# MC_power_en.net
KiCad netlist of a schematic drawn in Altium Designer
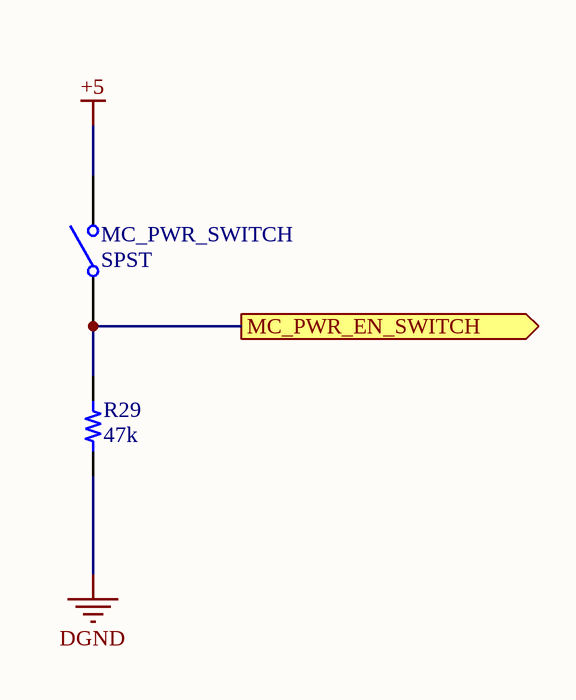
[diagram p0: MC_power_en.SchDoc]

(export (version "E")
  (design (tool "Eeschema 10.0.6"))
  (components
    (comp (ref "MC_PWR_SWITCH")
      (value "SPST")
      (footprint "M2011SS1W01/UC")
      (fields (field (name "MFRPARTNO") "M2011SS1W01_UC"))
      (libsource (lib "Altium-Lib") (part "SPST"))
    )
    (comp (ref "R29")
      (value "47k")
      (footprint "RES 0805/2012")
      (fields
        (field (name "TOLERANCE") "10%")
        (field (name "POWER") "1/4W")
        (field (name "Comment") "Resistor 47k 0805 1/4W 10%")
        (field (name "CREATED_BY") "Nick Mah")
      )
      (libsource (lib "Altium-Lib") (part "Resistor"))
    )
  )
  (nets
    (net (code "1") (name "+5") (class "Default")
      (node (ref "MC_PWR_SWITCH") (pin "2") (pinfunction "NO_2") (pintype "passive"))
    )
    (net (code "2") (name "/MC_PWR_EN_SWITCH") (class "Default")
      (node (ref "MC_PWR_SWITCH") (pin "1") (pinfunction "COMMON_1") (pintype "passive"))
      (node (ref "R29") (pin "2") (pinfunction "2_2") (pintype "passive"))
    )
    (net (code "3") (name "DGND") (class "Default")
      (node (ref "R29") (pin "1") (pinfunction "1_1") (pintype "passive"))
    )
  )
)
